# Lipo_uCharger.net
KiCad netlist of a schematic drawn in EAGLE
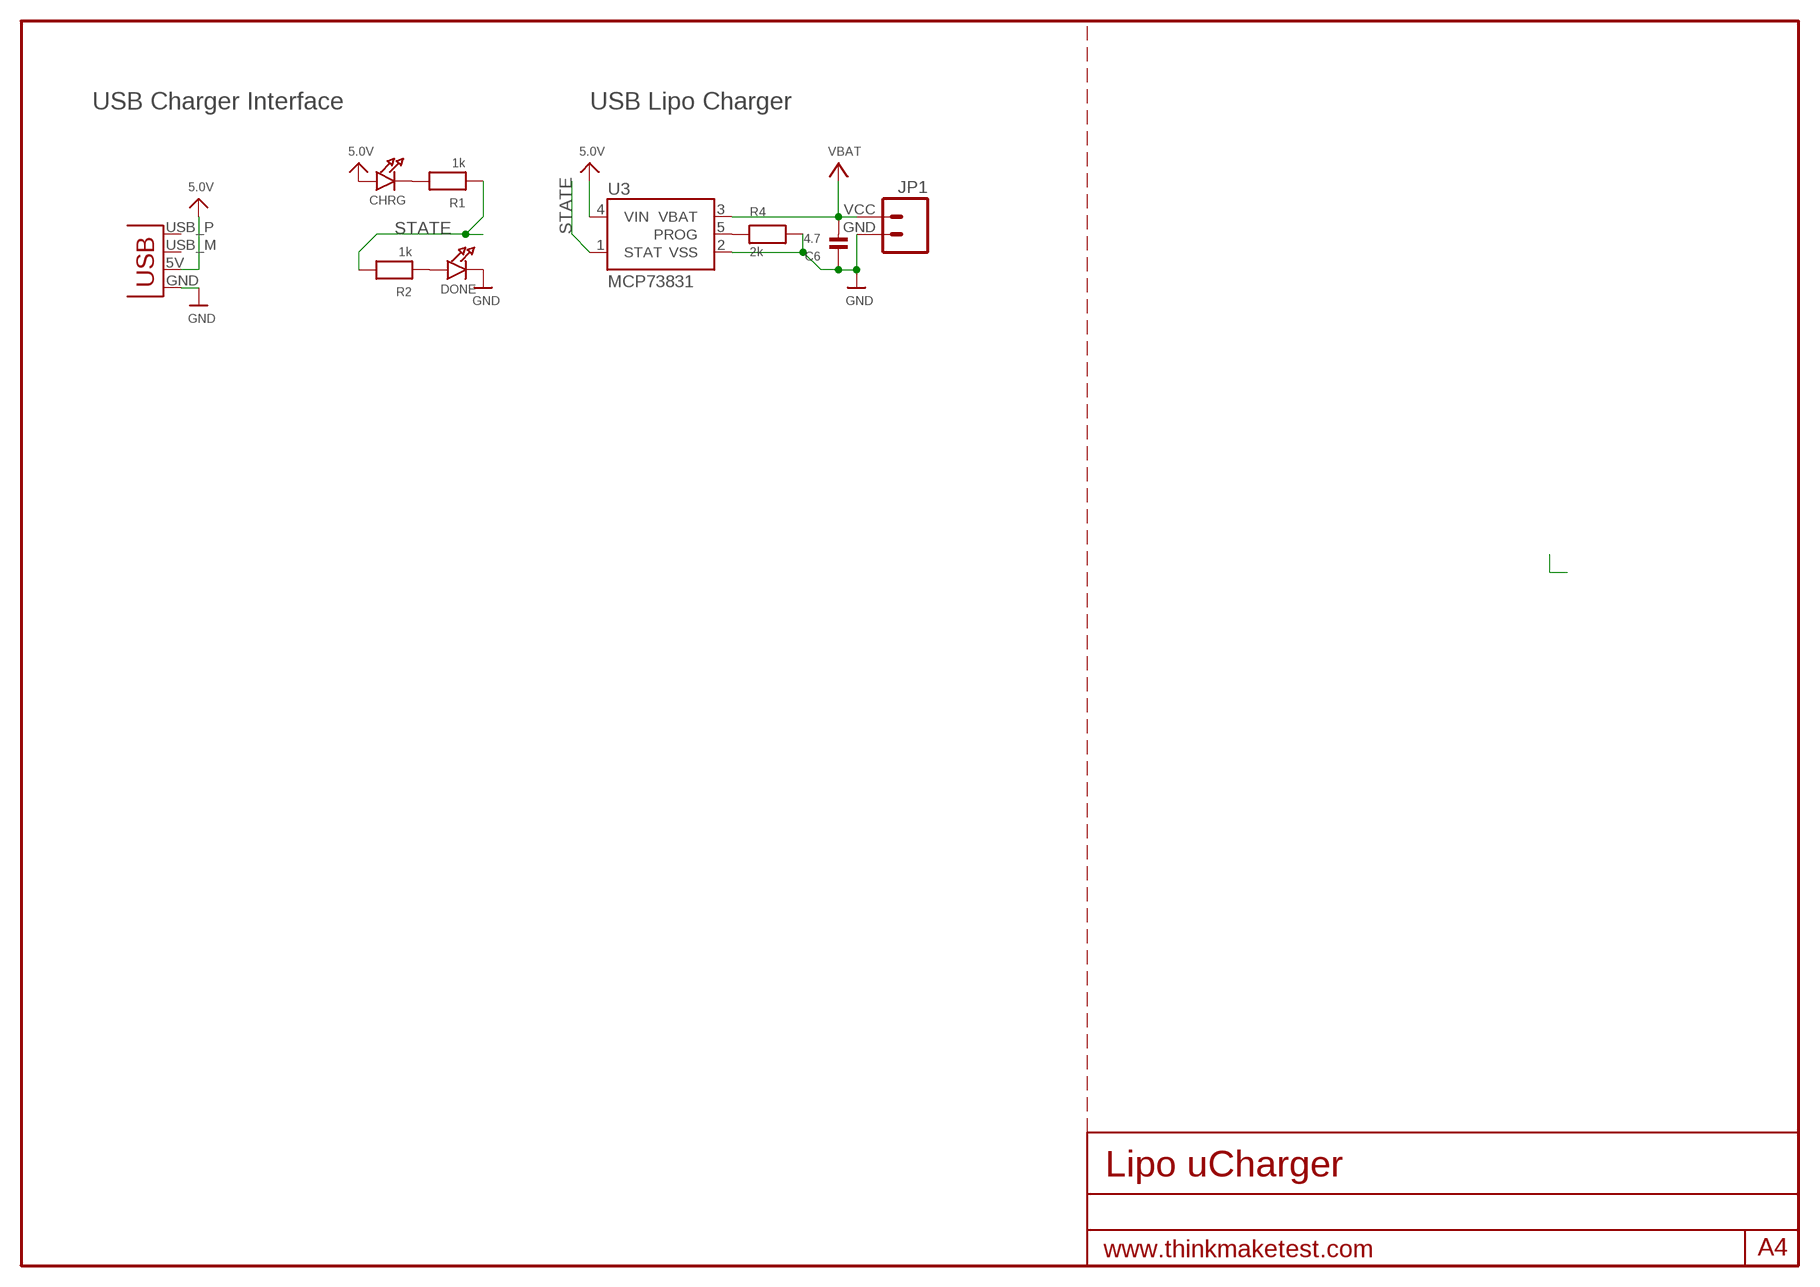
[diagram p0: schematic, sheet 1]

(export (version "E")
  (design (tool "Eeschema 10.0.6"))
  (components
    (comp (ref "C6")
      (value "4.7")
      (footprint "eagle-import:0603")
      (libsource (lib "eagle-import") (part "CAP_CERAMIC0603"))
    )
    (comp (ref "CHRG")
      (value "LED0603")
      (footprint "eagle-import:CHIPLED_0603")
      (libsource (lib "eagle-import") (part "LED0603"))
    )
    (comp (ref "DONE")
      (value "LED0603")
      (footprint "eagle-import:CHIPLED_0603")
      (libsource (lib "eagle-import") (part "LED0603"))
    )
    (comp (ref "JP1")
      (value "M024UCON-15767")
      (footprint "eagle-import:JST-2-SMD-VERT")
      (libsource (lib "eagle-import") (part "M024UCON-15767"))
    )
    (comp (ref "R1")
      (value "1k")
      (footprint "eagle-import:0603")
      (libsource (lib "eagle-import") (part "RESISTOR0603"))
    )
    (comp (ref "R2")
      (value "1k")
      (footprint "eagle-import:0603")
      (libsource (lib "eagle-import") (part "RESISTOR0603"))
    )
    (comp (ref "R4")
      (value "2k")
      (footprint "eagle-import:0603")
      (libsource (lib "eagle-import") (part "RESISTOR0603"))
    )
    (comp (ref "U3")
      (value "MCP73831")
      (footprint "eagle-import:SOT23-5")
      (libsource (lib "eagle-import") (part "MCP73831"))
    )
    (comp (ref "X1")
      (value "USBPCB")
      (footprint "eagle-import:USB-A-PCB")
      (libsource (lib "eagle-import") (part "USBPCB"))
    )
  )
  (nets
    (net (code "1") (name "/STATE") (class "Default")
      (node (ref "R1") (pin "1") (pinfunction "1_1") (pintype "passive"))
      (node (ref "R2") (pin "2") (pinfunction "2_2") (pintype "passive"))
      (node (ref "U3") (pin "1") (pinfunction "STAT_1") (pintype "output"))
    )
    (net (code "2") (name "5.0V") (class "Default")
      (node (ref "CHRG") (pin "A") (pinfunction "A_A") (pintype "passive"))
      (node (ref "U3") (pin "4") (pinfunction "VIN_4") (pintype "power_in"))
      (node (ref "X1") (pin "5V") (pinfunction "VBUS_5V") (pintype "bidirectional"))
    )
    (net (code "3") (name "GND") (class "Default")
      (node (ref "C6") (pin "1") (pinfunction "P$1_1") (pintype "passive"))
      (node (ref "DONE") (pin "C") (pinfunction "C_C") (pintype "passive"))
      (node (ref "JP1") (pin "GND") (pinfunction "1_GND") (pintype "passive"))
      (node (ref "R4") (pin "2") (pinfunction "2_2") (pintype "passive"))
      (node (ref "U3") (pin "2") (pinfunction "VSS_2") (pintype "power_in"))
      (node (ref "X1") (pin "GND") (pinfunction "GND_GND") (pintype "bidirectional"))
    )
    (net (code "4") (name "Net-(CHRG-PadC)") (class "Default")
      (node (ref "CHRG") (pin "C") (pinfunction "C_C") (pintype "passive"))
      (node (ref "R1") (pin "2") (pinfunction "2_2") (pintype "passive"))
    )
    (net (code "5") (name "Net-(DONE-PadA)") (class "Default")
      (node (ref "DONE") (pin "A") (pinfunction "A_A") (pintype "passive"))
      (node (ref "R2") (pin "1") (pinfunction "1_1") (pintype "passive"))
    )
    (net (code "6") (name "Net-(U3-PROG)") (class "Default")
      (node (ref "R4") (pin "1") (pinfunction "1_1") (pintype "passive"))
      (node (ref "U3") (pin "5") (pinfunction "PROG_5") (pintype "input"))
    )
    (net (code "7") (name "VBAT") (class "Default")
      (node (ref "C6") (pin "2") (pinfunction "P$2_2") (pintype "passive"))
      (node (ref "JP1") (pin "VCC") (pinfunction "2_VCC") (pintype "passive"))
      (node (ref "U3") (pin "3") (pinfunction "VBAT_3") (pintype "power_in"))
    )
    (net (code "8") (name "unconnected-(X1-D+-PadUSB_P)") (class "Default")
      (node (ref "X1") (pin "USB_P") (pinfunction "D+_USB_P") (pintype "bidirectional"))
    )
    (net (code "9") (name "unconnected-(X1-D--PadUSB_M)") (class "Default")
      (node (ref "X1") (pin "USB_M") (pinfunction "D-_USB_M") (pintype "bidirectional"))
    )
  )
)
